# PadSwitcher64_dip.net
KiCad netlist of a schematic drawn in EAGLE
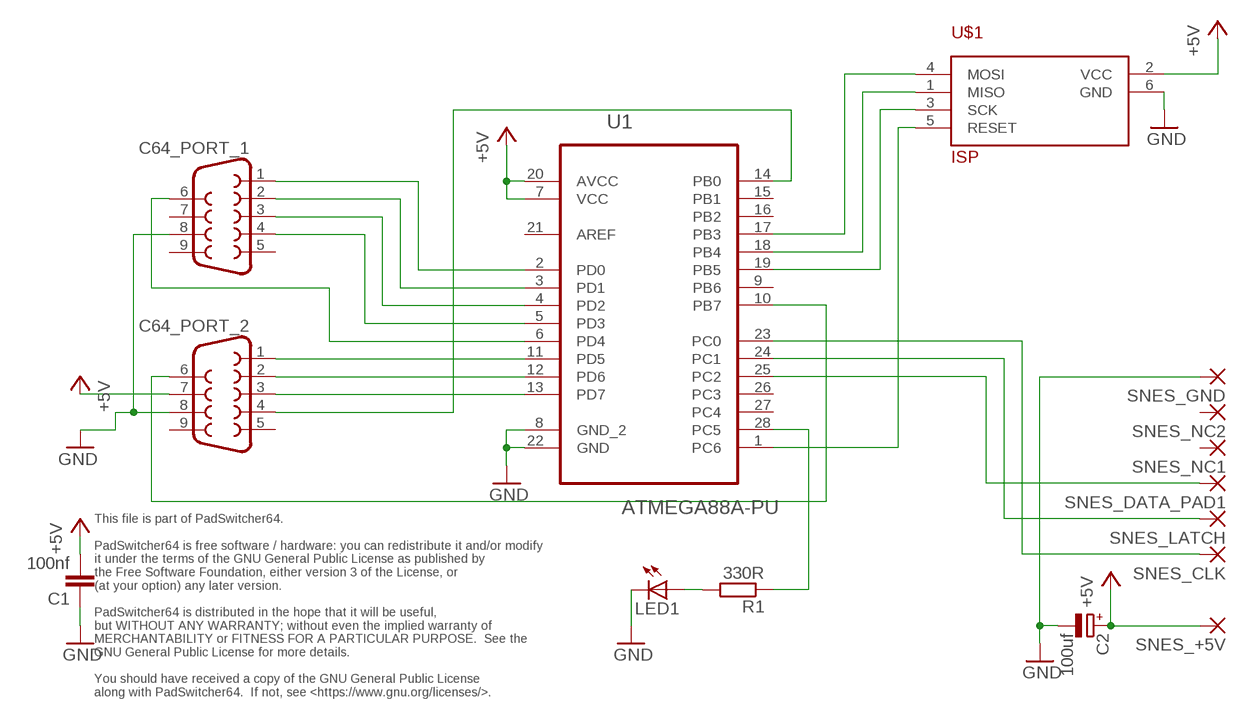
[diagram p0: schematic, sheet 1]

(export (version "E")
  (design (tool "Eeschema 10.0.6"))
  (components
    (comp (ref "C1")
      (value "100nf")
      (footprint "eagle-import:C050-024X044")
      (libsource (lib "eagle-import") (part "C-EU050-024X044"))
    )
    (comp (ref "C2")
      (value "100uf")
      (footprint "eagle-import:E2,5-5")
      (libsource (lib "eagle-import") (part "CPOL-EUE2.5-5"))
    )
    (comp (ref "C64_PORT_1")
      (value "F09")
      (footprint "eagle-import:F09VB_NO_SHELL")
      (libsource (lib "eagle-import") (part "F09"))
    )
    (comp (ref "C64_PORT_2")
      (value "F09")
      (footprint "eagle-import:F09VB_NO_SHELL")
      (libsource (lib "eagle-import") (part "F09"))
    )
    (comp (ref "LED1")
      (value "LEDSQR2X5")
      (footprint "eagle-import:LED2X5")
      (libsource (lib "eagle-import") (part "LEDSQR2X5"))
    )
    (comp (ref "R1")
      (value "330R")
      (footprint "eagle-import:0207_10")
      (libsource (lib "eagle-import") (part "R-EU_0207/10"))
    )
    (comp (ref "SNES_+5V")
      (value "3,17/1,1")
      (footprint "eagle-import:3,17_1,1")
      (libsource (lib "eagle-import") (part "3,17/1,1"))
    )
    (comp (ref "SNES_CLK")
      (value "3,17/1,1")
      (footprint "eagle-import:3,17_1,1")
      (libsource (lib "eagle-import") (part "3,17/1,1"))
    )
    (comp (ref "SNES_DATA_PAD1")
      (value "3,17/1,1")
      (footprint "eagle-import:3,17_1,1")
      (libsource (lib "eagle-import") (part "3,17/1,1"))
    )
    (comp (ref "SNES_GND")
      (value "3,17/1,1")
      (footprint "eagle-import:3,17_1,1")
      (libsource (lib "eagle-import") (part "3,17/1,1"))
    )
    (comp (ref "SNES_LATCH")
      (value "3,17/1,1")
      (footprint "eagle-import:3,17_1,1")
      (libsource (lib "eagle-import") (part "3,17/1,1"))
    )
    (comp (ref "SNES_NC1")
      (value "3,17/1,1")
      (footprint "eagle-import:3,17_1,1")
      (libsource (lib "eagle-import") (part "3,17/1,1"))
    )
    (comp (ref "SNES_NC2")
      (value "3,17/1,1")
      (footprint "eagle-import:3,17_1,1")
      (libsource (lib "eagle-import") (part "3,17/1,1"))
    )
    (comp (ref "U$1")
      (value "ISP")
      (footprint "eagle-import:MA03-2")
      (libsource (lib "eagle-import") (part "AVR_ISP6"))
    )
    (comp (ref "U1")
      (value "ATMEGA88A-PU")
      (footprint "eagle-import:DIL28-3")
      (libsource (lib "eagle-import") (part "ATMEGA88A-PU"))
    )
  )
  (nets
    (net (code "1") (name "+5V") (class "Default")
      (node (ref "C1") (pin "2") (pinfunction "2_2") (pintype "passive"))
      (node (ref "C2") (pin "+") (pinfunction "+_+") (pintype "passive"))
      (node (ref "C64_PORT_2") (pin "7") (pinfunction "7_7") (pintype "passive"))
      (node (ref "SNES_+5V") (pin "1") (pinfunction "P_1") (pintype "passive"))
      (node (ref "U$1") (pin "2") (pinfunction "VCC_2") (pintype "bidirectional"))
      (node (ref "U1") (pin "20") (pinfunction "AVCC_20") (pintype "power_in"))
      (node (ref "U1") (pin "7") (pinfunction "VCC_7") (pintype "power_in"))
    )
    (net (code "2") (name "GND") (class "Default")
      (node (ref "C1") (pin "1") (pinfunction "1_1") (pintype "passive"))
      (node (ref "C2") (pin "-") (pinfunction "-_-") (pintype "passive"))
      (node (ref "C64_PORT_1") (pin "8") (pinfunction "8_8") (pintype "passive"))
      (node (ref "C64_PORT_2") (pin "8") (pinfunction "8_8") (pintype "passive"))
      (node (ref "LED1") (pin "K") (pinfunction "C_K") (pintype "passive"))
      (node (ref "SNES_GND") (pin "1") (pinfunction "P_1") (pintype "passive"))
      (node (ref "U$1") (pin "6") (pinfunction "GND_6") (pintype "bidirectional"))
      (node (ref "U1") (pin "22") (pinfunction "GND_22") (pintype "passive"))
      (node (ref "U1") (pin "8") (pinfunction "GND_2_8") (pintype "passive"))
    )
    (net (code "3") (name "Net-(LED1-PadA)") (class "Default")
      (node (ref "LED1") (pin "A") (pinfunction "A_A") (pintype "passive"))
      (node (ref "R1") (pin "2") (pinfunction "2_2") (pintype "passive"))
    )
    (net (code "4") (name "Net-(SNES_CLK-P)") (class "Default")
      (node (ref "SNES_CLK") (pin "1") (pinfunction "P_1") (pintype "passive"))
      (node (ref "U1") (pin "23") (pinfunction "PC0_23") (pintype "bidirectional"))
    )
    (net (code "5") (name "Net-(SNES_DATA_PAD1-P)") (class "Default")
      (node (ref "SNES_DATA_PAD1") (pin "1") (pinfunction "P_1") (pintype "passive"))
      (node (ref "U1") (pin "25") (pinfunction "PC2_25") (pintype "bidirectional"))
    )
    (net (code "6") (name "Net-(SNES_LATCH-P)") (class "Default")
      (node (ref "SNES_LATCH") (pin "1") (pinfunction "P_1") (pintype "passive"))
      (node (ref "U1") (pin "24") (pinfunction "PC1_24") (pintype "bidirectional"))
    )
    (net (code "7") (name "Net-(U$1-MISO)") (class "Default")
      (node (ref "U$1") (pin "1") (pinfunction "MISO_1") (pintype "bidirectional"))
      (node (ref "U1") (pin "18") (pinfunction "PB4_18") (pintype "bidirectional"))
    )
    (net (code "8") (name "Net-(U$1-MOSI)") (class "Default")
      (node (ref "U$1") (pin "4") (pinfunction "MOSI_4") (pintype "bidirectional"))
      (node (ref "U1") (pin "17") (pinfunction "PB3_17") (pintype "bidirectional"))
    )
    (net (code "9") (name "Net-(U$1-RESET)") (class "Default")
      (node (ref "U$1") (pin "5") (pinfunction "RESET_5") (pintype "bidirectional"))
      (node (ref "U1") (pin "1") (pinfunction "PC6_1") (pintype "bidirectional"))
    )
    (net (code "10") (name "Net-(U$1-SCK)") (class "Default")
      (node (ref "U$1") (pin "3") (pinfunction "SCK_3") (pintype "bidirectional"))
      (node (ref "U1") (pin "19") (pinfunction "PB5_19") (pintype "bidirectional"))
    )
    (net (code "11") (name "Net-(U1-PB0)") (class "Default")
      (node (ref "C64_PORT_2") (pin "4") (pinfunction "4_4") (pintype "passive"))
      (node (ref "U1") (pin "14") (pinfunction "PB0_14") (pintype "bidirectional"))
    )
    (net (code "12") (name "Net-(U1-PB7)") (class "Default")
      (node (ref "C64_PORT_2") (pin "6") (pinfunction "6_6") (pintype "passive"))
      (node (ref "U1") (pin "10") (pinfunction "PB7_10") (pintype "bidirectional"))
    )
    (net (code "13") (name "Net-(U1-PC5)") (class "Default")
      (node (ref "R1") (pin "1") (pinfunction "1_1") (pintype "passive"))
      (node (ref "U1") (pin "28") (pinfunction "PC5_28") (pintype "bidirectional"))
    )
    (net (code "14") (name "Net-(U1-PD0)") (class "Default")
      (node (ref "C64_PORT_1") (pin "1") (pinfunction "1_1") (pintype "passive"))
      (node (ref "U1") (pin "2") (pinfunction "PD0_2") (pintype "bidirectional"))
    )
    (net (code "15") (name "Net-(U1-PD1)") (class "Default")
      (node (ref "C64_PORT_1") (pin "2") (pinfunction "2_2") (pintype "passive"))
      (node (ref "U1") (pin "3") (pinfunction "PD1_3") (pintype "bidirectional"))
    )
    (net (code "16") (name "Net-(U1-PD2)") (class "Default")
      (node (ref "C64_PORT_1") (pin "3") (pinfunction "3_3") (pintype "passive"))
      (node (ref "U1") (pin "4") (pinfunction "PD2_4") (pintype "bidirectional"))
    )
    (net (code "17") (name "Net-(U1-PD3)") (class "Default")
      (node (ref "C64_PORT_1") (pin "4") (pinfunction "4_4") (pintype "passive"))
      (node (ref "U1") (pin "5") (pinfunction "PD3_5") (pintype "bidirectional"))
    )
    (net (code "18") (name "Net-(U1-PD4)") (class "Default")
      (node (ref "C64_PORT_1") (pin "6") (pinfunction "6_6") (pintype "passive"))
      (node (ref "U1") (pin "6") (pinfunction "PD4_6") (pintype "bidirectional"))
    )
    (net (code "19") (name "Net-(U1-PD5)") (class "Default")
      (node (ref "C64_PORT_2") (pin "1") (pinfunction "1_1") (pintype "passive"))
      (node (ref "U1") (pin "11") (pinfunction "PD5_11") (pintype "bidirectional"))
    )
    (net (code "20") (name "Net-(U1-PD6)") (class "Default")
      (node (ref "C64_PORT_2") (pin "2") (pinfunction "2_2") (pintype "passive"))
      (node (ref "U1") (pin "12") (pinfunction "PD6_12") (pintype "bidirectional"))
    )
    (net (code "21") (name "Net-(U1-PD7)") (class "Default")
      (node (ref "C64_PORT_2") (pin "3") (pinfunction "3_3") (pintype "passive"))
      (node (ref "U1") (pin "13") (pinfunction "PD7_13") (pintype "bidirectional"))
    )
    (net (code "22") (name "unconnected-(C64_PORT_1-Pad5)") (class "Default")
      (node (ref "C64_PORT_1") (pin "5") (pinfunction "5_5") (pintype "passive"))
    )
    (net (code "23") (name "unconnected-(C64_PORT_1-Pad7)") (class "Default")
      (node (ref "C64_PORT_1") (pin "7") (pinfunction "7_7") (pintype "passive"))
    )
    (net (code "24") (name "unconnected-(C64_PORT_1-Pad9)") (class "Default")
      (node (ref "C64_PORT_1") (pin "9") (pinfunction "9_9") (pintype "passive"))
    )
    (net (code "25") (name "unconnected-(C64_PORT_2-Pad5)") (class "Default")
      (node (ref "C64_PORT_2") (pin "5") (pinfunction "5_5") (pintype "passive"))
    )
    (net (code "26") (name "unconnected-(C64_PORT_2-Pad9)") (class "Default")
      (node (ref "C64_PORT_2") (pin "9") (pinfunction "9_9") (pintype "passive"))
    )
    (net (code "27") (name "unconnected-(SNES_NC1-P-Pad1)") (class "Default")
      (node (ref "SNES_NC1") (pin "1") (pinfunction "P_1") (pintype "passive"))
    )
    (net (code "28") (name "unconnected-(SNES_NC2-P-Pad1)") (class "Default")
      (node (ref "SNES_NC2") (pin "1") (pinfunction "P_1") (pintype "passive"))
    )
    (net (code "29") (name "unconnected-(U1-AREF-Pad21)") (class "Default")
      (node (ref "U1") (pin "21") (pinfunction "AREF_21") (pintype "input"))
    )
    (net (code "30") (name "unconnected-(U1-PB1-Pad15)") (class "Default")
      (node (ref "U1") (pin "15") (pinfunction "PB1_15") (pintype "bidirectional"))
    )
    (net (code "31") (name "unconnected-(U1-PB2-Pad16)") (class "Default")
      (node (ref "U1") (pin "16") (pinfunction "PB2_16") (pintype "bidirectional"))
    )
    (net (code "32") (name "unconnected-(U1-PB6-Pad9)") (class "Default")
      (node (ref "U1") (pin "9") (pinfunction "PB6_9") (pintype "bidirectional"))
    )
    (net (code "33") (name "unconnected-(U1-PC3-Pad26)") (class "Default")
      (node (ref "U1") (pin "26") (pinfunction "PC3_26") (pintype "bidirectional"))
    )
    (net (code "34") (name "unconnected-(U1-PC4-Pad27)") (class "Default")
      (node (ref "U1") (pin "27") (pinfunction "PC4_27") (pintype "bidirectional"))
    )
  )
)
